# nfc-attiny-atecc.net
KiCad netlist of a schematic drawn in EAGLE
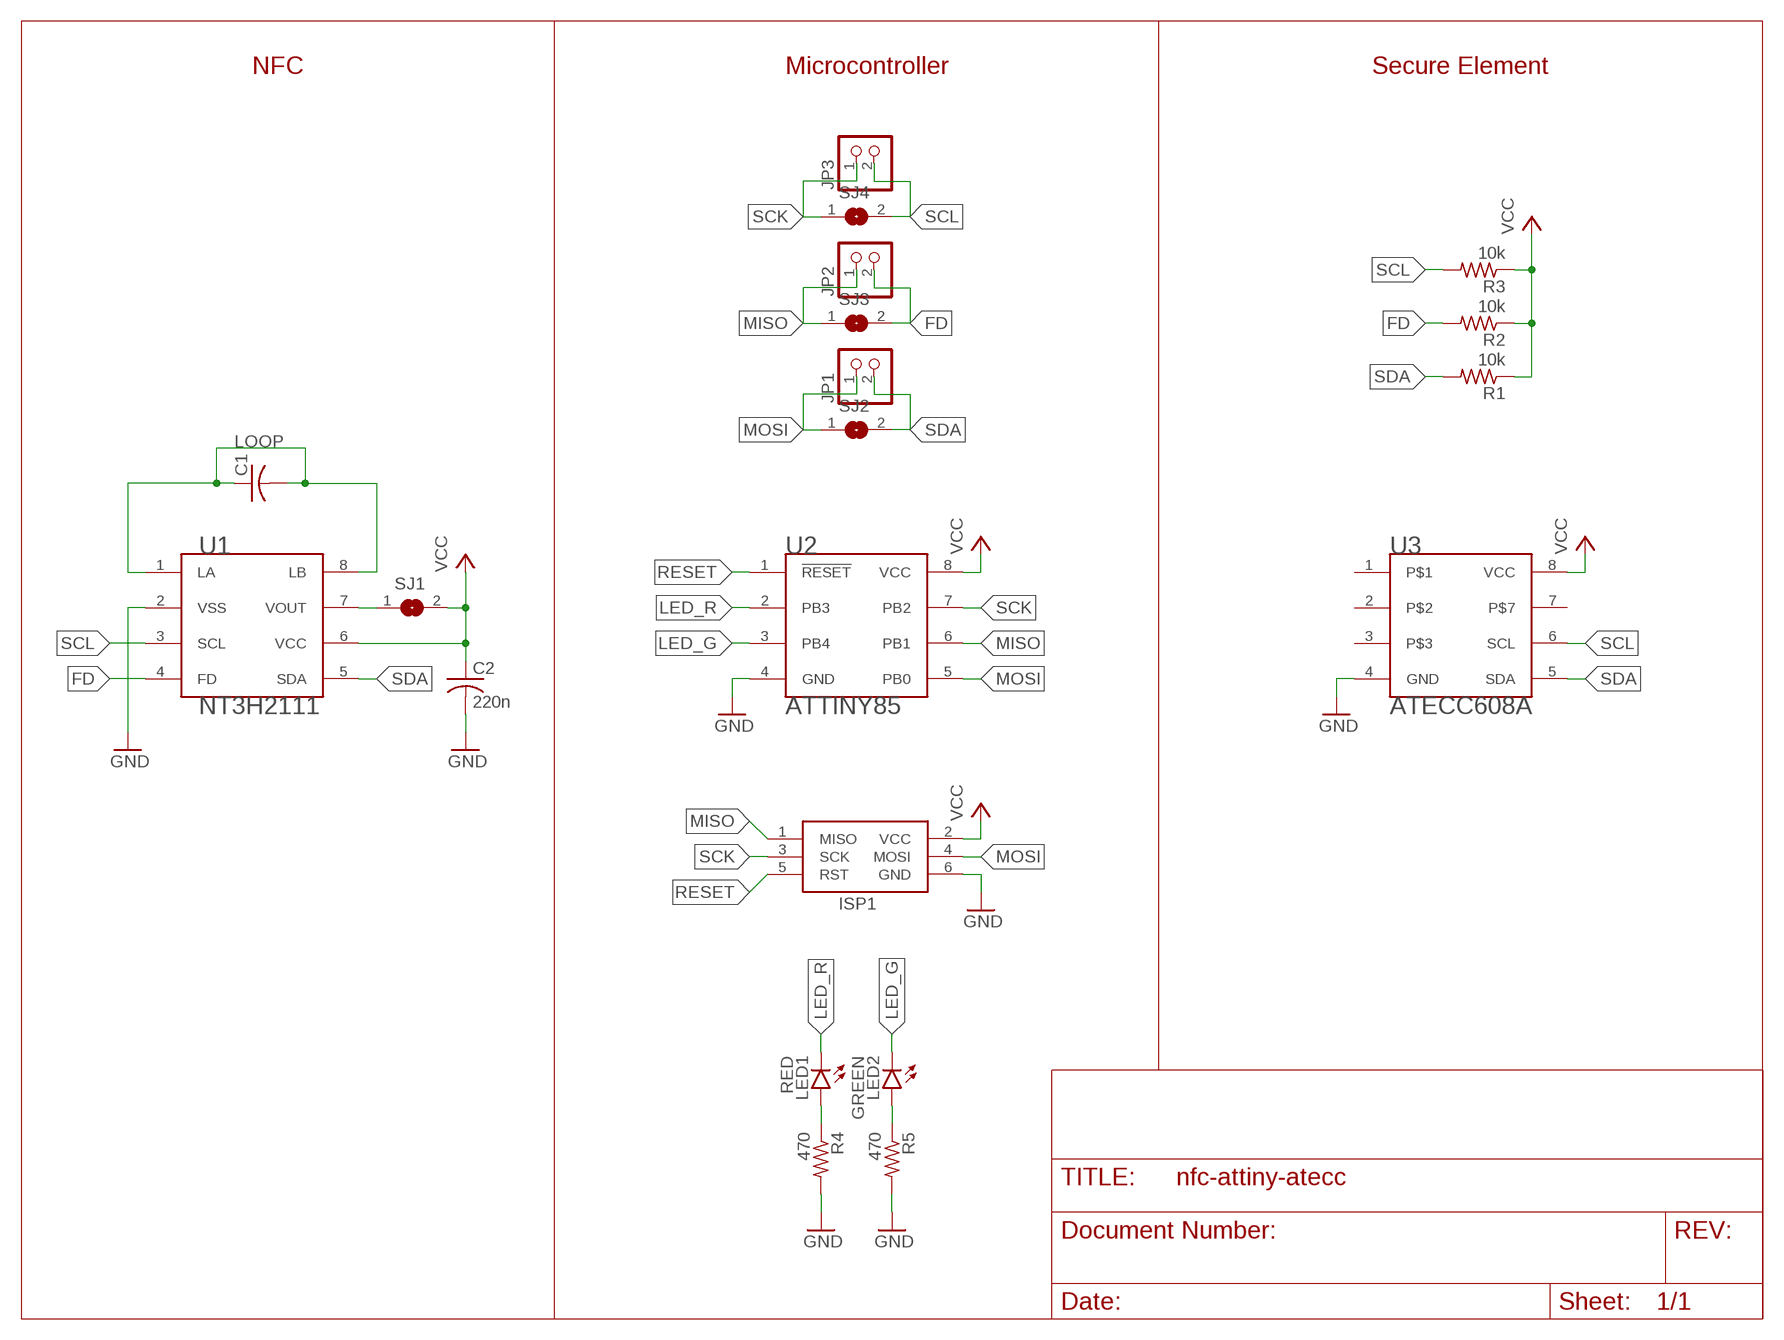
[diagram p0: schematic, sheet 1]

(export (version "E")
  (design (tool "Eeschema 10.0.6"))
  (components
    (comp (ref "C1")
      (value "C-USC0805")
      (footprint "eagle-import:C0805")
      (libsource (lib "eagle-import") (part "C-USC0805"))
    )
    (comp (ref "C2")
      (value "220n")
      (footprint "eagle-import:C0805")
      (libsource (lib "eagle-import") (part "C-USC0805"))
    )
    (comp (ref "ISP1")
      (value "AVRISP-BOX")
      (footprint "eagle-import:AVRISP-BOX")
      (libsource (lib "eagle-import") (part "AVRISP-BOX"))
    )
    (comp (ref "JP1")
      (value "PINHD-1X2")
      (footprint "eagle-import:1X02")
      (libsource (lib "eagle-import") (part "PINHD-1X2"))
    )
    (comp (ref "JP2")
      (value "PINHD-1X2")
      (footprint "eagle-import:1X02")
      (libsource (lib "eagle-import") (part "PINHD-1X2"))
    )
    (comp (ref "JP3")
      (value "PINHD-1X2")
      (footprint "eagle-import:1X02")
      (libsource (lib "eagle-import") (part "PINHD-1X2"))
    )
    (comp (ref "LED1")
      (value "RED")
      (footprint "eagle-import:CHIP-LED0805")
      (libsource (lib "eagle-import") (part "LEDCHIP-LED0805"))
    )
    (comp (ref "LED2")
      (value "GREEN")
      (footprint "eagle-import:CHIP-LED0805")
      (libsource (lib "eagle-import") (part "LEDCHIP-LED0805"))
    )
    (comp (ref "R1")
      (value "10k")
      (footprint "eagle-import:R0805")
      (libsource (lib "eagle-import") (part "R-US_R0805"))
    )
    (comp (ref "R2")
      (value "10k")
      (footprint "eagle-import:R0805")
      (libsource (lib "eagle-import") (part "R-US_R0805"))
    )
    (comp (ref "R3")
      (value "10k")
      (footprint "eagle-import:R0805")
      (libsource (lib "eagle-import") (part "R-US_R0805"))
    )
    (comp (ref "R4")
      (value "470")
      (footprint "eagle-import:R0805")
      (libsource (lib "eagle-import") (part "R-US_R0805"))
    )
    (comp (ref "R5")
      (value "470")
      (footprint "eagle-import:R0805")
      (libsource (lib "eagle-import") (part "R-US_R0805"))
    )
    (comp (ref "SJ1") (value "SJ") (footprint "eagle-import:SJ") (libsource (lib "eagle-import") (part "SJ")))
    (comp (ref "SJ2") (value "SJ") (footprint "eagle-import:SJ") (libsource (lib "eagle-import") (part "SJ")))
    (comp (ref "SJ3") (value "SJ") (footprint "eagle-import:SJ") (libsource (lib "eagle-import") (part "SJ")))
    (comp (ref "SJ4") (value "SJ") (footprint "eagle-import:SJ") (libsource (lib "eagle-import") (part "SJ")))
    (comp (ref "U1")
      (value "NT3H2111")
      (footprint "eagle-import:SOIC127P600X175-8N")
      (fields (field (name "MPN") "NT3H2111W0FT1X"))
      (libsource (lib "eagle-import") (part "NT3H2111-SOIC8"))
    )
    (comp (ref "U2")
      (value "ATTINY85")
      (footprint "eagle-import:SOIC127P797X215-8N")
      (fields (field (name "MPN") "ATTINY85V-10SU"))
      (libsource (lib "eagle-import") (part "ATTINY85-SOIC8"))
    )
    (comp (ref "U3")
      (value "ATECC608A")
      (footprint "eagle-import:SOIC127P600X175-8N")
      (libsource (lib "eagle-import") (part "ATECC608A-SOIC8"))
    )
  )
  (nets
    (net (code "1") (name "/LOOP") (class "Default")
      (node (ref "C1") (pin "1") (pinfunction "1_1") (pintype "passive"))
      (node (ref "C1") (pin "2") (pinfunction "2_2") (pintype "passive"))
      (node (ref "U1") (pin "1") (pinfunction "LA_1") (pintype "bidirectional"))
      (node (ref "U1") (pin "8") (pinfunction "LB_8") (pintype "bidirectional"))
    )
    (net (code "2") (name "FD") (class "Default")
      (node (ref "JP2") (pin "2") (pinfunction "2_2") (pintype "passive"))
      (node (ref "R2") (pin "2") (pinfunction "2_2") (pintype "passive"))
      (node (ref "SJ3") (pin "2") (pinfunction "2_2") (pintype "passive"))
      (node (ref "U1") (pin "4") (pinfunction "FD_4") (pintype "bidirectional"))
    )
    (net (code "3") (name "GND") (class "Default")
      (node (ref "C2") (pin "2") (pinfunction "2_2") (pintype "passive"))
      (node (ref "ISP1") (pin "6") (pinfunction "GND_6") (pintype "power_in"))
      (node (ref "R4") (pin "2") (pinfunction "2_2") (pintype "passive"))
      (node (ref "R5") (pin "2") (pinfunction "2_2") (pintype "passive"))
      (node (ref "U1") (pin "2") (pinfunction "VSS_2") (pintype "bidirectional"))
      (node (ref "U2") (pin "4") (pinfunction "GND_4") (pintype "bidirectional"))
      (node (ref "U3") (pin "4") (pinfunction "GND_4") (pintype "bidirectional"))
    )
    (net (code "4") (name "LED_G") (class "Default")
      (node (ref "LED2") (pin "C") (pinfunction "C_C") (pintype "passive"))
      (node (ref "U2") (pin "3") (pinfunction "PB4_3") (pintype "bidirectional"))
    )
    (net (code "5") (name "LED_R") (class "Default")
      (node (ref "LED1") (pin "C") (pinfunction "C_C") (pintype "passive"))
      (node (ref "U2") (pin "2") (pinfunction "PB3_2") (pintype "bidirectional"))
    )
    (net (code "6") (name "MISO") (class "Default")
      (node (ref "ISP1") (pin "1") (pinfunction "MISO_1") (pintype "input"))
      (node (ref "JP2") (pin "1") (pinfunction "1_1") (pintype "passive"))
      (node (ref "SJ3") (pin "1") (pinfunction "1_1") (pintype "passive"))
      (node (ref "U2") (pin "6") (pinfunction "PB1_6") (pintype "bidirectional"))
    )
    (net (code "7") (name "MOSI") (class "Default")
      (node (ref "ISP1") (pin "4") (pinfunction "MOSI_4") (pintype "output"))
      (node (ref "JP1") (pin "1") (pinfunction "1_1") (pintype "passive"))
      (node (ref "SJ2") (pin "1") (pinfunction "1_1") (pintype "passive"))
      (node (ref "U2") (pin "5") (pinfunction "PB0_5") (pintype "bidirectional"))
    )
    (net (code "8") (name "Net-(LED1-PadA)") (class "Default")
      (node (ref "LED1") (pin "A") (pinfunction "A_A") (pintype "passive"))
      (node (ref "R4") (pin "1") (pinfunction "1_1") (pintype "passive"))
    )
    (net (code "9") (name "Net-(LED2-PadA)") (class "Default")
      (node (ref "LED2") (pin "A") (pinfunction "A_A") (pintype "passive"))
      (node (ref "R5") (pin "1") (pinfunction "1_1") (pintype "passive"))
    )
    (net (code "10") (name "Net-(U1-VOUT)") (class "Default")
      (node (ref "SJ1") (pin "1") (pinfunction "1_1") (pintype "passive"))
      (node (ref "U1") (pin "7") (pinfunction "VOUT_7") (pintype "bidirectional"))
    )
    (net (code "11") (name "RESET") (class "Default")
      (node (ref "ISP1") (pin "5") (pinfunction "RST_5") (pintype "output"))
      (node (ref "U2") (pin "1") (pinfunction "~{RESET}_1") (pintype "bidirectional"))
    )
    (net (code "12") (name "SCK") (class "Default")
      (node (ref "ISP1") (pin "3") (pinfunction "SCK_3") (pintype "output"))
      (node (ref "JP3") (pin "1") (pinfunction "1_1") (pintype "passive"))
      (node (ref "SJ4") (pin "1") (pinfunction "1_1") (pintype "passive"))
      (node (ref "U2") (pin "7") (pinfunction "PB2_7") (pintype "bidirectional"))
    )
    (net (code "13") (name "SCL") (class "Default")
      (node (ref "JP3") (pin "2") (pinfunction "2_2") (pintype "passive"))
      (node (ref "R3") (pin "2") (pinfunction "2_2") (pintype "passive"))
      (node (ref "SJ4") (pin "2") (pinfunction "2_2") (pintype "passive"))
      (node (ref "U1") (pin "3") (pinfunction "SCL_3") (pintype "bidirectional"))
      (node (ref "U3") (pin "6") (pinfunction "SCL_6") (pintype "bidirectional"))
    )
    (net (code "14") (name "SDA") (class "Default")
      (node (ref "JP1") (pin "2") (pinfunction "2_2") (pintype "passive"))
      (node (ref "R1") (pin "2") (pinfunction "2_2") (pintype "passive"))
      (node (ref "SJ2") (pin "2") (pinfunction "2_2") (pintype "passive"))
      (node (ref "U1") (pin "5") (pinfunction "SDA_5") (pintype "bidirectional"))
      (node (ref "U3") (pin "5") (pinfunction "SDA_5") (pintype "bidirectional"))
    )
    (net (code "15") (name "VCC") (class "Default")
      (node (ref "C2") (pin "1") (pinfunction "1_1") (pintype "passive"))
      (node (ref "ISP1") (pin "2") (pinfunction "VCC_2") (pintype "power_in"))
      (node (ref "R1") (pin "1") (pinfunction "1_1") (pintype "passive"))
      (node (ref "R2") (pin "1") (pinfunction "1_1") (pintype "passive"))
      (node (ref "R3") (pin "1") (pinfunction "1_1") (pintype "passive"))
      (node (ref "SJ1") (pin "2") (pinfunction "2_2") (pintype "passive"))
      (node (ref "U1") (pin "6") (pinfunction "VCC_6") (pintype "bidirectional"))
      (node (ref "U2") (pin "8") (pinfunction "VCC_8") (pintype "bidirectional"))
      (node (ref "U3") (pin "8") (pinfunction "VCC_8") (pintype "bidirectional"))
    )
    (net (code "16") (name "unconnected-(U3-P$1-Pad1)") (class "Default")
      (node (ref "U3") (pin "1") (pinfunction "P$1_1") (pintype "no_connect"))
    )
    (net (code "17") (name "unconnected-(U3-P$2-Pad2)") (class "Default")
      (node (ref "U3") (pin "2") (pinfunction "P$2_2") (pintype "no_connect"))
    )
    (net (code "18") (name "unconnected-(U3-P$3-Pad3)") (class "Default")
      (node (ref "U3") (pin "3") (pinfunction "P$3_3") (pintype "no_connect"))
    )
    (net (code "19") (name "unconnected-(U3-P$7-Pad7)") (class "Default")
      (node (ref "U3") (pin "7") (pinfunction "P$7_7") (pintype "no_connect"))
    )
  )
)
